# untitled.net
KiCad netlist of a schematic drawn in EAGLE
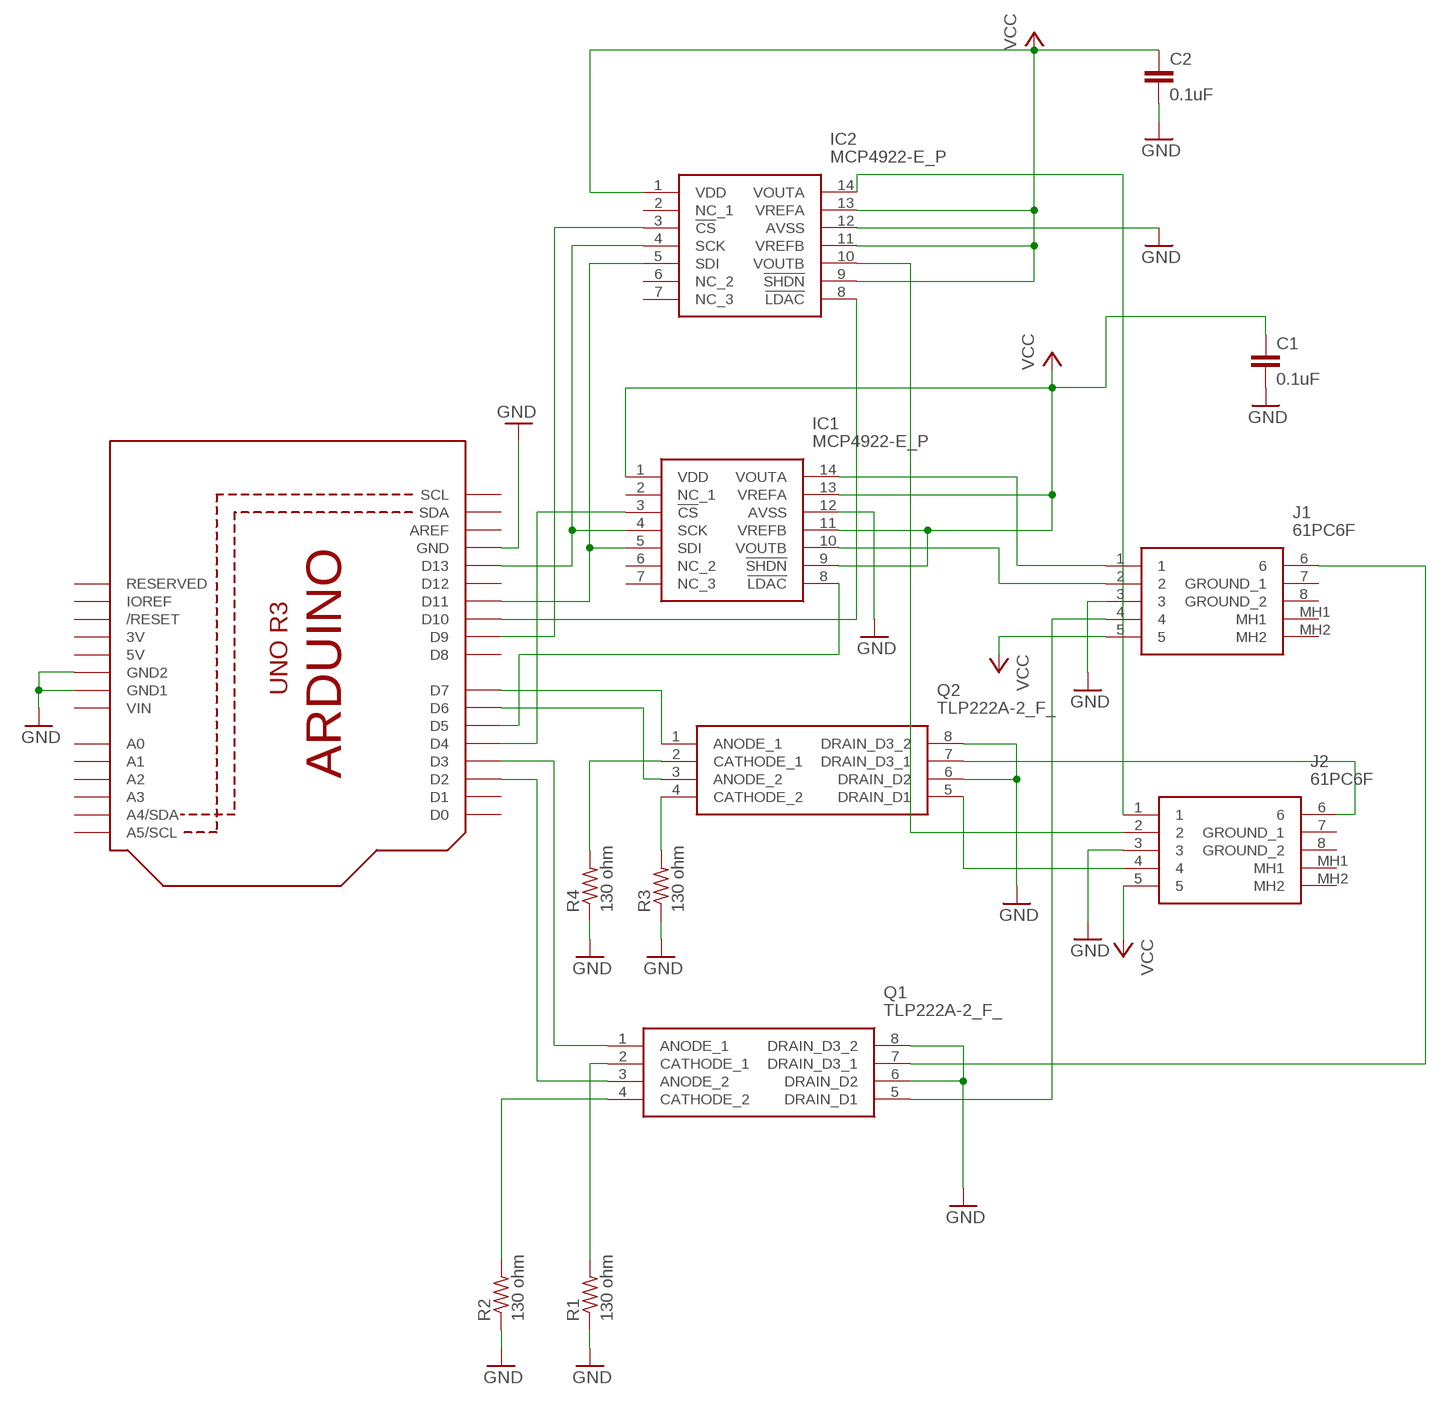
[diagram p0: schematic, sheet 1]

(export (version "E")
  (design (tool "Eeschema 10.0.6"))
  (components
    (comp (ref "C1")
      (value "0.1uF")
      (footprint "eagle-import:C050-024X044")
      (libsource (lib "eagle-import") (part "C-EU050-024X044"))
    )
    (comp (ref "C2")
      (value "0.1uF")
      (footprint "eagle-import:C050-024X044")
      (libsource (lib "eagle-import") (part "C-EU050-024X044"))
    )
    (comp (ref "IC1")
      (value "MCP4922-E_P")
      (footprint "eagle-import:DIP794W56P254L1905H432Q14N")
      (fields
        (field (name "MANUFACTURER_PART_NUMBER") "MCP4922-E/P")
        (field (name "MOUSER_PART_NUMBER") "579-MCP4922-E/P")
      )
      (libsource (lib "eagle-import") (part "MCP4922-E_P"))
    )
    (comp (ref "IC2")
      (value "MCP4922-E_P")
      (footprint "eagle-import:DIP794W56P254L1905H432Q14N")
      (fields
        (field (name "MANUFACTURER_PART_NUMBER") "MCP4922-E/P")
        (field (name "MOUSER_PART_NUMBER") "579-MCP4922-E/P")
      )
      (libsource (lib "eagle-import") (part "MCP4922-E_P"))
    )
    (comp (ref "J1")
      (value "61PC6F")
      (footprint "eagle-import:61PC6F")
      (fields (field (name "MOUSER_PART_NUMBER") "502-61PC6F"))
      (libsource (lib "eagle-import") (part "61PC6F"))
    )
    (comp (ref "J2")
      (value "61PC6F")
      (footprint "eagle-import:61PC6F")
      (fields (field (name "MOUSER_PART_NUMBER") "502-61PC6F"))
      (libsource (lib "eagle-import") (part "61PC6F"))
    )
    (comp (ref "Q1")
      (value "TLP222A-2_F_")
      (footprint "eagle-import:DIP762W60P254L966H485Q8N")
      (fields
        (field (name "MANUFACTURER_PART_NUMBER") "TLP222A-2(F)")
        (field (name "MOUSER_PART_NUMBER") "757-TLP222A-2(F)")
      )
      (libsource (lib "eagle-import") (part "TLP222A-2_F_"))
    )
    (comp (ref "Q2")
      (value "TLP222A-2_F_")
      (footprint "eagle-import:DIP762W60P254L966H485Q8N")
      (fields
        (field (name "MANUFACTURER_PART_NUMBER") "TLP222A-2(F)")
        (field (name "MOUSER_PART_NUMBER") "757-TLP222A-2(F)")
      )
      (libsource (lib "eagle-import") (part "TLP222A-2_F_"))
    )
    (comp (ref "R1")
      (value "130 ohm")
      (footprint "eagle-import:0207_7")
      (libsource (lib "eagle-import") (part "R-US_0207/7"))
    )
    (comp (ref "R2")
      (value "130 ohm")
      (footprint "eagle-import:0207_7")
      (libsource (lib "eagle-import") (part "R-US_0207/7"))
    )
    (comp (ref "R3")
      (value "130 ohm")
      (footprint "eagle-import:0207_7")
      (libsource (lib "eagle-import") (part "R-US_0207/7"))
    )
    (comp (ref "R4")
      (value "130 ohm")
      (footprint "eagle-import:0207_7")
      (libsource (lib "eagle-import") (part "R-US_0207/7"))
    )
    (comp (ref "U1")
      (value "ARDUINOR3-BPLACE")
      (footprint "eagle-import:ARDUINOR3-BPLACE")
      (libsource (lib "eagle-import") (part "ARDUINOR3-BPLACE"))
    )
  )
  (nets
    (net (code "1") (name "/3V") (class "Default")
      (node (ref "U1") (pin "3V") (pinfunction "3V_3V") (pintype "power_in"))
    )
    (net (code "2") (name "/5V") (class "Default")
      (node (ref "U1") (pin "5V") (pinfunction "5V_5V") (pintype "power_in"))
    )
    (net (code "3") (name "/VIN") (class "Default")
      (node (ref "U1") (pin "VIN") (pinfunction "VIN_VIN") (pintype "power_in"))
    )
    (net (code "4") (name "GND") (class "Default")
      (node (ref "C1") (pin "2") (pinfunction "2_2") (pintype "passive"))
      (node (ref "C2") (pin "2") (pinfunction "2_2") (pintype "passive"))
      (node (ref "IC1") (pin "12") (pinfunction "AVSS_12") (pintype "bidirectional"))
      (node (ref "IC2") (pin "12") (pinfunction "AVSS_12") (pintype "bidirectional"))
      (node (ref "J1") (pin "3") (pinfunction "3_3") (pintype "bidirectional"))
      (node (ref "J2") (pin "3") (pinfunction "3_3") (pintype "bidirectional"))
      (node (ref "Q1") (pin "6") (pinfunction "DRAIN_D2_6") (pintype "bidirectional"))
      (node (ref "Q1") (pin "8") (pinfunction "DRAIN_D3_2_8") (pintype "bidirectional"))
      (node (ref "Q2") (pin "6") (pinfunction "DRAIN_D2_6") (pintype "bidirectional"))
      (node (ref "Q2") (pin "8") (pinfunction "DRAIN_D3_2_8") (pintype "bidirectional"))
      (node (ref "R1") (pin "1") (pinfunction "1_1") (pintype "passive"))
      (node (ref "R2") (pin "1") (pinfunction "1_1") (pintype "passive"))
      (node (ref "R3") (pin "1") (pinfunction "1_1") (pintype "passive"))
      (node (ref "R4") (pin "1") (pinfunction "1_1") (pintype "passive"))
      (node (ref "U1") (pin "GND") (pinfunction "GND_GND") (pintype "power_in"))
      (node (ref "U1") (pin "GND1") (pinfunction "GND1_GND1") (pintype "power_in"))
      (node (ref "U1") (pin "GND2") (pinfunction "GND2_GND2") (pintype "power_in"))
    )
    (net (code "5") (name "Net-(IC1-SCK)") (class "Default")
      (node (ref "IC1") (pin "4") (pinfunction "SCK_4") (pintype "bidirectional"))
      (node (ref "IC2") (pin "4") (pinfunction "SCK_4") (pintype "bidirectional"))
      (node (ref "U1") (pin "D13") (pinfunction "D13_D13") (pintype "bidirectional"))
    )
    (net (code "6") (name "Net-(IC1-SDI)") (class "Default")
      (node (ref "IC1") (pin "5") (pinfunction "SDI_5") (pintype "bidirectional"))
      (node (ref "IC2") (pin "5") (pinfunction "SDI_5") (pintype "bidirectional"))
      (node (ref "U1") (pin "D11") (pinfunction "D11_D11") (pintype "bidirectional"))
    )
    (net (code "7") (name "Net-(IC1-VOUTA)") (class "Default")
      (node (ref "IC1") (pin "14") (pinfunction "VOUTA_14") (pintype "bidirectional"))
      (node (ref "J1") (pin "1") (pinfunction "1_1") (pintype "bidirectional"))
    )
    (net (code "8") (name "Net-(IC1-VOUTB)") (class "Default")
      (node (ref "IC1") (pin "10") (pinfunction "VOUTB_10") (pintype "bidirectional"))
      (node (ref "J1") (pin "2") (pinfunction "2_2") (pintype "bidirectional"))
    )
    (net (code "9") (name "Net-(IC1-~{CS})") (class "Default")
      (node (ref "IC1") (pin "3") (pinfunction "~{CS}_3") (pintype "bidirectional"))
      (node (ref "U1") (pin "D4") (pinfunction "D4_D4") (pintype "bidirectional"))
    )
    (net (code "10") (name "Net-(IC1-~{LDAC})") (class "Default")
      (node (ref "IC1") (pin "8") (pinfunction "~{LDAC}_8") (pintype "bidirectional"))
      (node (ref "U1") (pin "D5") (pinfunction "D5_D5") (pintype "bidirectional"))
    )
    (net (code "11") (name "Net-(IC2-VOUTA)") (class "Default")
      (node (ref "IC2") (pin "14") (pinfunction "VOUTA_14") (pintype "bidirectional"))
      (node (ref "J2") (pin "1") (pinfunction "1_1") (pintype "bidirectional"))
    )
    (net (code "12") (name "Net-(IC2-VOUTB)") (class "Default")
      (node (ref "IC2") (pin "10") (pinfunction "VOUTB_10") (pintype "bidirectional"))
      (node (ref "J2") (pin "2") (pinfunction "2_2") (pintype "bidirectional"))
    )
    (net (code "13") (name "Net-(IC2-~{CS})") (class "Default")
      (node (ref "IC2") (pin "3") (pinfunction "~{CS}_3") (pintype "bidirectional"))
      (node (ref "U1") (pin "D9") (pinfunction "D9_D9") (pintype "bidirectional"))
    )
    (net (code "14") (name "Net-(IC2-~{LDAC})") (class "Default")
      (node (ref "IC2") (pin "8") (pinfunction "~{LDAC}_8") (pintype "bidirectional"))
      (node (ref "U1") (pin "D10") (pinfunction "D10_D10") (pintype "bidirectional"))
    )
    (net (code "15") (name "Net-(Q1-ANODE_1)") (class "Default")
      (node (ref "Q1") (pin "1") (pinfunction "ANODE_1_1") (pintype "bidirectional"))
      (node (ref "U1") (pin "D3") (pinfunction "D3_D3") (pintype "bidirectional"))
    )
    (net (code "16") (name "Net-(Q1-ANODE_2)") (class "Default")
      (node (ref "Q1") (pin "3") (pinfunction "ANODE_2_3") (pintype "bidirectional"))
      (node (ref "U1") (pin "D2") (pinfunction "D2_D2") (pintype "bidirectional"))
    )
    (net (code "17") (name "Net-(Q1-CATHODE_1)") (class "Default")
      (node (ref "Q1") (pin "2") (pinfunction "CATHODE_1_2") (pintype "bidirectional"))
      (node (ref "R1") (pin "2") (pinfunction "2_2") (pintype "passive"))
    )
    (net (code "18") (name "Net-(Q1-CATHODE_2)") (class "Default")
      (node (ref "Q1") (pin "4") (pinfunction "CATHODE_2_4") (pintype "bidirectional"))
      (node (ref "R2") (pin "2") (pinfunction "2_2") (pintype "passive"))
    )
    (net (code "19") (name "Net-(Q1-DRAIN_D1)") (class "Default")
      (node (ref "J1") (pin "4") (pinfunction "4_4") (pintype "bidirectional"))
      (node (ref "Q1") (pin "5") (pinfunction "DRAIN_D1_5") (pintype "bidirectional"))
    )
    (net (code "20") (name "Net-(Q1-DRAIN_D3_1)") (class "Default")
      (node (ref "J1") (pin "6") (pinfunction "6_6") (pintype "bidirectional"))
      (node (ref "Q1") (pin "7") (pinfunction "DRAIN_D3_1_7") (pintype "bidirectional"))
    )
    (net (code "21") (name "Net-(Q2-ANODE_1)") (class "Default")
      (node (ref "Q2") (pin "1") (pinfunction "ANODE_1_1") (pintype "bidirectional"))
      (node (ref "U1") (pin "D7") (pinfunction "D7_D7") (pintype "bidirectional"))
    )
    (net (code "22") (name "Net-(Q2-ANODE_2)") (class "Default")
      (node (ref "Q2") (pin "3") (pinfunction "ANODE_2_3") (pintype "bidirectional"))
      (node (ref "U1") (pin "D6") (pinfunction "D6_D6") (pintype "bidirectional"))
    )
    (net (code "23") (name "Net-(Q2-CATHODE_1)") (class "Default")
      (node (ref "Q2") (pin "2") (pinfunction "CATHODE_1_2") (pintype "bidirectional"))
      (node (ref "R4") (pin "2") (pinfunction "2_2") (pintype "passive"))
    )
    (net (code "24") (name "Net-(Q2-CATHODE_2)") (class "Default")
      (node (ref "Q2") (pin "4") (pinfunction "CATHODE_2_4") (pintype "bidirectional"))
      (node (ref "R3") (pin "2") (pinfunction "2_2") (pintype "passive"))
    )
    (net (code "25") (name "Net-(Q2-DRAIN_D1)") (class "Default")
      (node (ref "J2") (pin "4") (pinfunction "4_4") (pintype "bidirectional"))
      (node (ref "Q2") (pin "5") (pinfunction "DRAIN_D1_5") (pintype "bidirectional"))
    )
    (net (code "26") (name "Net-(Q2-DRAIN_D3_1)") (class "Default")
      (node (ref "J2") (pin "6") (pinfunction "6_6") (pintype "bidirectional"))
      (node (ref "Q2") (pin "7") (pinfunction "DRAIN_D3_1_7") (pintype "bidirectional"))
    )
    (net (code "27") (name "VCC") (class "Default")
      (node (ref "C1") (pin "1") (pinfunction "1_1") (pintype "passive"))
      (node (ref "C2") (pin "1") (pinfunction "1_1") (pintype "passive"))
      (node (ref "IC1") (pin "1") (pinfunction "VDD_1") (pintype "bidirectional"))
      (node (ref "IC1") (pin "11") (pinfunction "VREFB_11") (pintype "bidirectional"))
      (node (ref "IC1") (pin "13") (pinfunction "VREFA_13") (pintype "bidirectional"))
      (node (ref "IC1") (pin "9") (pinfunction "~{SHDN}_9") (pintype "bidirectional"))
      (node (ref "IC2") (pin "1") (pinfunction "VDD_1") (pintype "bidirectional"))
      (node (ref "IC2") (pin "11") (pinfunction "VREFB_11") (pintype "bidirectional"))
      (node (ref "IC2") (pin "13") (pinfunction "VREFA_13") (pintype "bidirectional"))
      (node (ref "IC2") (pin "9") (pinfunction "~{SHDN}_9") (pintype "bidirectional"))
      (node (ref "J1") (pin "5") (pinfunction "5_5") (pintype "bidirectional"))
      (node (ref "J2") (pin "5") (pinfunction "5_5") (pintype "bidirectional"))
    )
    (net (code "28") (name "unconnected-(IC1-NC_1-Pad2)") (class "Default")
      (node (ref "IC1") (pin "2") (pinfunction "NC_1_2") (pintype "bidirectional"))
    )
    (net (code "29") (name "unconnected-(IC1-NC_2-Pad6)") (class "Default")
      (node (ref "IC1") (pin "6") (pinfunction "NC_2_6") (pintype "bidirectional"))
    )
    (net (code "30") (name "unconnected-(IC1-NC_3-Pad7)") (class "Default")
      (node (ref "IC1") (pin "7") (pinfunction "NC_3_7") (pintype "bidirectional"))
    )
    (net (code "31") (name "unconnected-(IC2-NC_1-Pad2)") (class "Default")
      (node (ref "IC2") (pin "2") (pinfunction "NC_1_2") (pintype "bidirectional"))
    )
    (net (code "32") (name "unconnected-(IC2-NC_2-Pad6)") (class "Default")
      (node (ref "IC2") (pin "6") (pinfunction "NC_2_6") (pintype "bidirectional"))
    )
    (net (code "33") (name "unconnected-(IC2-NC_3-Pad7)") (class "Default")
      (node (ref "IC2") (pin "7") (pinfunction "NC_3_7") (pintype "bidirectional"))
    )
    (net (code "34") (name "unconnected-(J1-GROUND_1-Pad7)") (class "Default")
      (node (ref "J1") (pin "7") (pinfunction "GROUND_1_7") (pintype "bidirectional"))
    )
    (net (code "35") (name "unconnected-(J1-GROUND_2-Pad8)") (class "Default")
      (node (ref "J1") (pin "8") (pinfunction "GROUND_2_8") (pintype "bidirectional"))
    )
    (net (code "36") (name "unconnected-(J1-PadMH1)") (class "Default")
      (node (ref "J1") (pin "MH1") (pinfunction "MH1_MH1") (pintype "bidirectional"))
    )
    (net (code "37") (name "unconnected-(J1-PadMH2)") (class "Default")
      (node (ref "J1") (pin "MH2") (pinfunction "MH2_MH2") (pintype "bidirectional"))
    )
    (net (code "38") (name "unconnected-(J2-GROUND_1-Pad7)") (class "Default")
      (node (ref "J2") (pin "7") (pinfunction "GROUND_1_7") (pintype "bidirectional"))
    )
    (net (code "39") (name "unconnected-(J2-GROUND_2-Pad8)") (class "Default")
      (node (ref "J2") (pin "8") (pinfunction "GROUND_2_8") (pintype "bidirectional"))
    )
    (net (code "40") (name "unconnected-(J2-PadMH1)") (class "Default")
      (node (ref "J2") (pin "MH1") (pinfunction "MH1_MH1") (pintype "bidirectional"))
    )
    (net (code "41") (name "unconnected-(J2-PadMH2)") (class "Default")
      (node (ref "J2") (pin "MH2") (pinfunction "MH2_MH2") (pintype "bidirectional"))
    )
    (net (code "42") (name "unconnected-(U1-A4{slash}SDA-PadA4)") (class "Default")
      (node (ref "U1") (pin "A4") (pinfunction "A4/SDA_A4") (pintype "bidirectional"))
    )
    (net (code "43") (name "unconnected-(U1-A5{slash}SCL-PadA5)") (class "Default")
      (node (ref "U1") (pin "A5") (pinfunction "A5/SCL_A5") (pintype "bidirectional"))
    )
    (net (code "44") (name "unconnected-(U1-PadA0)") (class "Default")
      (node (ref "U1") (pin "A0") (pinfunction "A0_A0") (pintype "bidirectional"))
    )
    (net (code "45") (name "unconnected-(U1-PadA1)") (class "Default")
      (node (ref "U1") (pin "A1") (pinfunction "A1_A1") (pintype "bidirectional"))
    )
    (net (code "46") (name "unconnected-(U1-PadA2)") (class "Default")
      (node (ref "U1") (pin "A2") (pinfunction "A2_A2") (pintype "bidirectional"))
    )
    (net (code "47") (name "unconnected-(U1-PadA3)") (class "Default")
      (node (ref "U1") (pin "A3") (pinfunction "A3_A3") (pintype "bidirectional"))
    )
    (net (code "48") (name "unconnected-(U1-PadAREF)") (class "Default")
      (node (ref "U1") (pin "AREF") (pinfunction "AREF_AREF") (pintype "bidirectional"))
    )
    (net (code "49") (name "unconnected-(U1-PadD0)") (class "Default")
      (node (ref "U1") (pin "D0") (pinfunction "D0_D0") (pintype "bidirectional"))
    )
    (net (code "50") (name "unconnected-(U1-PadD1)") (class "Default")
      (node (ref "U1") (pin "D1") (pinfunction "D1_D1") (pintype "bidirectional"))
    )
    (net (code "51") (name "unconnected-(U1-PadD8)") (class "Default")
      (node (ref "U1") (pin "D8") (pinfunction "D8_D8") (pintype "bidirectional"))
    )
    (net (code "52") (name "unconnected-(U1-PadD12)") (class "Default")
      (node (ref "U1") (pin "D12") (pinfunction "D12_D12") (pintype "bidirectional"))
    )
    (net (code "53") (name "unconnected-(U1-PadIOREF)") (class "Default")
      (node (ref "U1") (pin "IOREF") (pinfunction "IOREF_IOREF") (pintype "output"))
    )
    (net (code "54") (name "unconnected-(U1-PadRESERVED)") (class "Default")
      (node (ref "U1") (pin "RESERVED") (pinfunction "RESERVED_RESERVED") (pintype "no_connect"))
    )
    (net (code "55") (name "unconnected-(U1-PadSCL)") (class "Default")
      (node (ref "U1") (pin "SCL") (pinfunction "SCL_SCL") (pintype "bidirectional"))
    )
    (net (code "56") (name "unconnected-(U1-PadSDA)") (class "Default")
      (node (ref "U1") (pin "SDA") (pinfunction "SDA_SDA") (pintype "bidirectional"))
    )
    (net (code "57") (name "unconnected-(U1-{slash}RESET-PadRESET)") (class "Default")
      (node (ref "U1") (pin "RESET") (pinfunction "/RESET_RESET") (pintype "bidirectional"))
    )
  )
)
